# 136khz_RX_2025-06-18.net
KiCad netlist of a schematic drawn in EasyEDA Pro
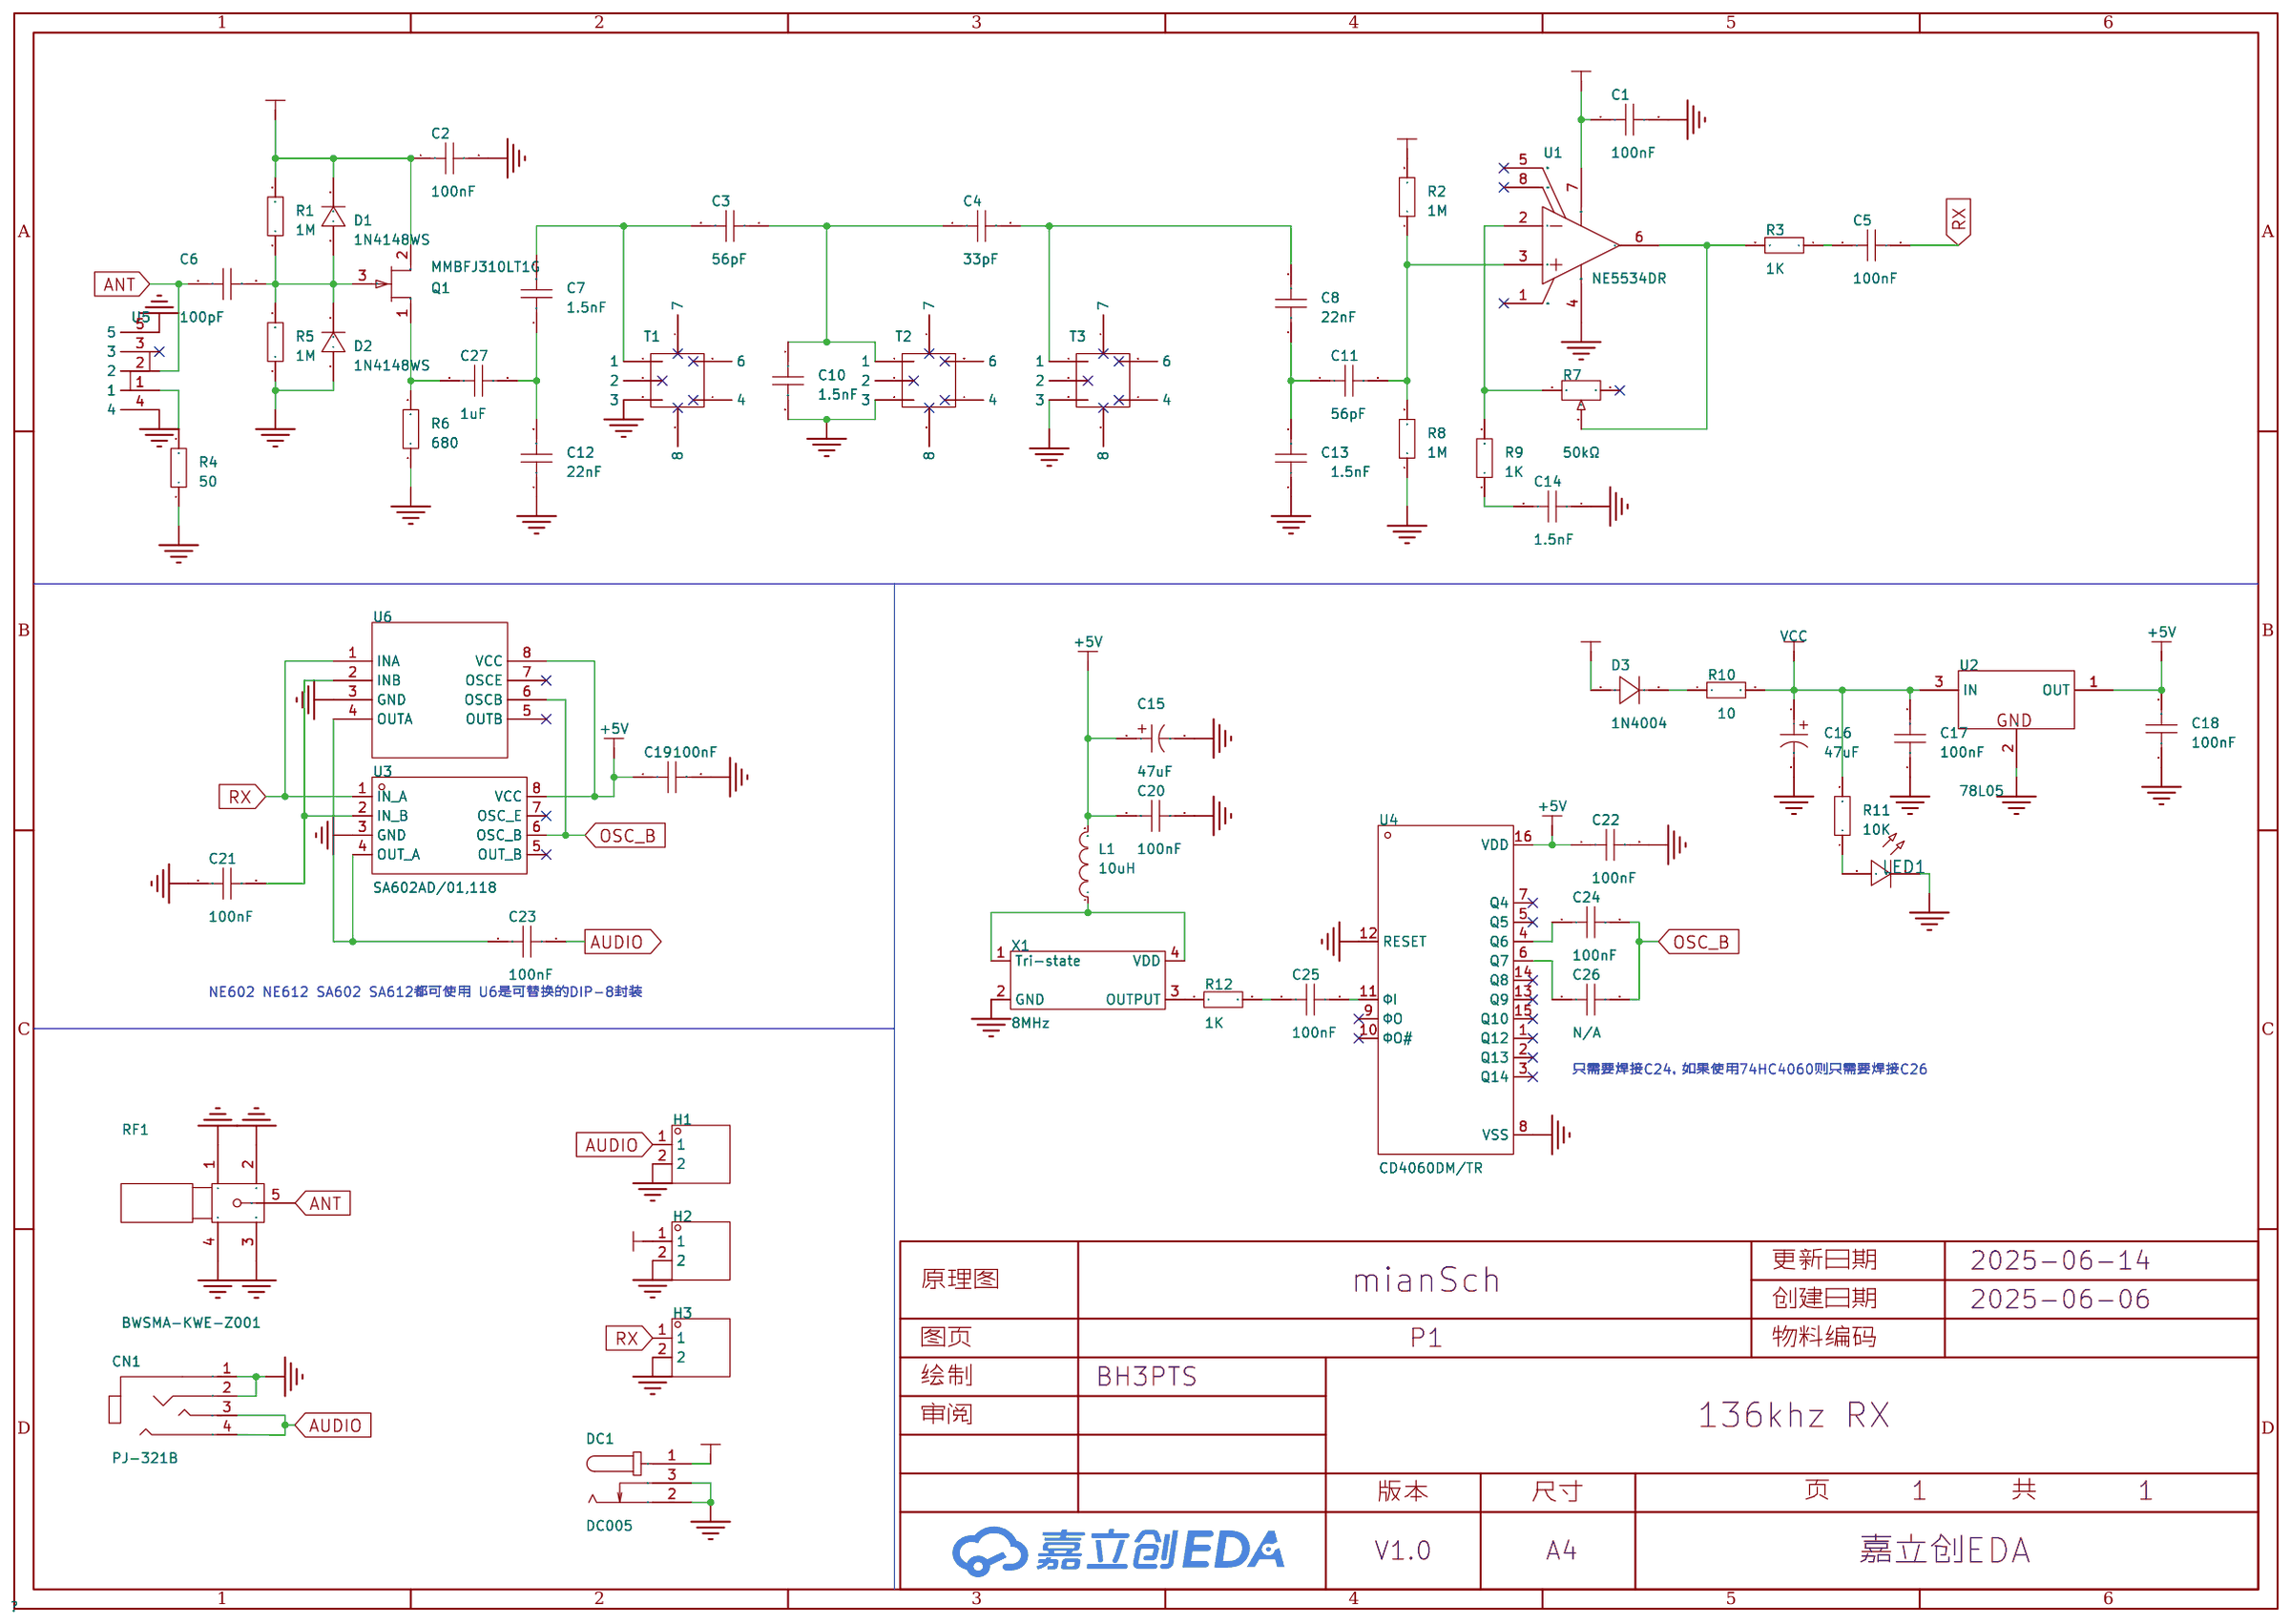
[diagram p0: schematic sheet]

(export (version "E")
  (design (tool "Eeschema 10.0.6"))
  (components
    (comp (ref "C1")
      (value "100nF")
      (footprint "easyedapro:C0805")
      (libsource (lib "easyedapro") (part "CapAcitance"))
    )
    (comp (ref "C2")
      (value "100nF")
      (footprint "easyedapro:C0805")
      (libsource (lib "easyedapro") (part "CapAcitance"))
    )
    (comp (ref "C3")
      (value "56pF")
      (footprint "easyedapro:C0805")
      (libsource (lib "easyedapro") (part "CapAcitance"))
    )
    (comp (ref "C4")
      (value "33pF")
      (footprint "easyedapro:C0805")
      (libsource (lib "easyedapro") (part "CapAcitance"))
    )
    (comp (ref "C5")
      (value "100nF")
      (footprint "easyedapro:C0805")
      (libsource (lib "easyedapro") (part "CapAcitance"))
    )
    (comp (ref "C6")
      (value "100pF")
      (footprint "easyedapro:C0805")
      (libsource (lib "easyedapro") (part "CapAcitance"))
    )
    (comp (ref "C7")
      (value "1.5nF")
      (footprint "easyedapro:C0805")
      (libsource (lib "easyedapro") (part "CapAcitance"))
    )
    (comp (ref "C8")
      (value "22nF")
      (footprint "easyedapro:C0805")
      (libsource (lib "easyedapro") (part "CapAcitance"))
    )
    (comp (ref "C10")
      (value "1.5nF")
      (footprint "easyedapro:C0805")
      (libsource (lib "easyedapro") (part "CapAcitance"))
    )
    (comp (ref "C11")
      (value "56pF")
      (footprint "easyedapro:C0805")
      (libsource (lib "easyedapro") (part "CapAcitance"))
    )
    (comp (ref "C12")
      (value "22nF")
      (footprint "easyedapro:C0805")
      (libsource (lib "easyedapro") (part "CapAcitance"))
    )
    (comp (ref "C13")
      (value "1.5nF")
      (footprint "easyedapro:C0805")
      (libsource (lib "easyedapro") (part "CapAcitance"))
    )
    (comp (ref "C14")
      (value "1.5nF")
      (footprint "easyedapro:C0805")
      (libsource (lib "easyedapro") (part "CapAcitance"))
    )
    (comp (ref "C15")
      (value "47uF")
      (footprint "easyedapro:CAP-SMD_BD6.3-L6.6-W6.6-LS7.2-FD")
      (description "容值:47uF;精度:±20%;额定电压:35V;纹波电流:16.4mA@120Hz;等效串联电阻(ESR):-;")
      (fields
        (field (name "Manufacturer Part") "RVT47UF35V67RV0039")
        (field (name "Manufacturer") "KNSCHA(科尼盛)")
      )
      (libsource (lib "easyedapro") (part "RVT47UF35V67RV0039"))
    )
    (comp (ref "C16")
      (value "47uF")
      (footprint "easyedapro:CAP-SMD_BD6.3-L6.6-W6.6-LS7.2-FD")
      (description "容值:47uF;精度:±20%;额定电压:35V;纹波电流:16.4mA@120Hz;等效串联电阻(ESR):-;")
      (fields
        (field (name "Manufacturer Part") "RVT47UF35V67RV0039")
        (field (name "Manufacturer") "KNSCHA(科尼盛)")
      )
      (libsource (lib "easyedapro") (part "RVT47UF35V67RV0039"))
    )
    (comp (ref "C17")
      (value "100nF")
      (footprint "easyedapro:C0805")
      (libsource (lib "easyedapro") (part "CapAcitance"))
    )
    (comp (ref "C18")
      (value "100nF")
      (footprint "easyedapro:C0805")
      (libsource (lib "easyedapro") (part "CapAcitance"))
    )
    (comp (ref "C19")
      (value "100nF")
      (footprint "easyedapro:C0805")
      (libsource (lib "easyedapro") (part "CapAcitance"))
    )
    (comp (ref "C20")
      (value "100nF")
      (footprint "easyedapro:C0805")
      (libsource (lib "easyedapro") (part "CapAcitance"))
    )
    (comp (ref "C21")
      (value "100nF")
      (footprint "easyedapro:C0805")
      (libsource (lib "easyedapro") (part "CapAcitance"))
    )
    (comp (ref "C22")
      (value "100nF")
      (footprint "easyedapro:C0805")
      (libsource (lib "easyedapro") (part "CapAcitance"))
    )
    (comp (ref "C23")
      (value "100nF")
      (footprint "easyedapro:C0805")
      (libsource (lib "easyedapro") (part "CapAcitance"))
    )
    (comp (ref "C24")
      (value "100nF")
      (footprint "easyedapro:C0805")
      (libsource (lib "easyedapro") (part "CapAcitance"))
    )
    (comp (ref "C25")
      (value "100nF")
      (footprint "easyedapro:C0805")
      (libsource (lib "easyedapro") (part "CapAcitance"))
    )
    (comp (ref "C26")
      (value "N/A")
      (footprint "easyedapro:C0805")
      (libsource (lib "easyedapro") (part "CapAcitance"))
    )
    (comp (ref "C27")
      (value "1uF")
      (footprint "easyedapro:C0805")
      (libsource (lib "easyedapro") (part "CapAcitance"))
    )
    (comp (ref "CN1")
      (value "PJ-321B")
      (footprint "easyedapro:AUDIO-TH_PJ-321B")
      (description "连接器类型:3.5mm耳机座;额定电流:500mA;额定电压:30V;工作温度范围:-20°C~+70°C;焊接温度(最大值):235°C;")
      (fields (field (name "Manufacturer") "XKB Connection(中国星坤)"))
      (libsource (lib "easyedapro") (part "PJ-321B"))
    )
    (comp (ref "D1")
      (value "1N4148WS")
      (footprint "easyedapro:SOD-323_L1.8-W1.3-LS2.5-RD")
      (description "二极管配置:独立式;正向压降(Vf):1.25V@150mA;直流反向耐压(Vr):100V;整流电流:150mA;反向恢复时间(trr):4ns;")
      (fields (field (name "Manufacturer") "CJ(江苏长电/长晶)"))
      (libsource (lib "easyedapro") (part "1N4148WS T4"))
    )
    (comp (ref "D2")
      (value "1N4148WS")
      (footprint "easyedapro:SOD-323_L1.8-W1.3-LS2.5-RD")
      (description "二极管配置:独立式;正向压降(Vf):1.25V@150mA;直流反向耐压(Vr):100V;整流电流:150mA;反向恢复时间(trr):4ns;")
      (fields (field (name "Manufacturer") "CJ(江苏长电/长晶)"))
      (libsource (lib "easyedapro") (part "1N4148WS T4"))
    )
    (comp (ref "D3")
      (value "1N4004")
      (footprint "easyedapro:SMA_L4.4-W2.8-LS5.4-RD")
      (description "二极管配置:独立式;正向压降(Vf):1.1V@1A;直流反向耐压(Vr):400V;整流电流:1A;")
      (fields (field (name "Manufacturer") "TWGMC(台湾迪嘉)"))
      (libsource (lib "easyedapro") (part "1N4004_C727080"))
    )
    (comp (ref "DC1")
      (value "DC005")
      (footprint "easyedapro:DC-IN-TH_DC005")
      (description "连接器类型:DC电源插座;安装方式:弯插;触点内径:2mm;触点外径:6.3mm;额定电流:500mA;额定电压:30V;工作温度范围:-25°C~+70°C;")
      (fields (field (name "Manufacturer") "SHOU HAN(首韩)"))
      (libsource (lib "easyedapro") (part "DC005_C431533"))
    )
    (comp (ref "H1")
      (value "~")
      (footprint "easyedapro:HDR-TH_2P-P2.54-V-M-1")
      (libsource (lib "easyedapro") (part "210S-1*2P L=11.6MMGold-plated black"))
    )
    (comp (ref "H2")
      (value "~")
      (footprint "easyedapro:HDR-TH_2P-P2.54-V-M-1")
      (libsource (lib "easyedapro") (part "210S-1*2P L=11.6MMGold-plated black"))
    )
    (comp (ref "H3")
      (value "~")
      (footprint "easyedapro:HDR-TH_2P-P2.54-V-M-1")
      (libsource (lib "easyedapro") (part "210S-1*2P L=11.6MMGold-plated black"))
    )
    (comp (ref "L1")
      (value "10uH")
      (footprint "easyedapro:L0603")
      (description "电感值:10uH;精度:±10%;额定电流:3mA;饱和电流(Isat):-;直流电阻(DCR):1.85Ω;")
      (fields
        (field (name "Manufacturer Part") "SDFL1608S100KTF")
        (field (name "Manufacturer") "Sunlord(顺络)")
      )
      (libsource (lib "easyedapro") (part "SDFL1608S100KTF"))
    )
    (comp (ref "LED1")
      (value "~")
      (footprint "easyedapro:LED_0603")
      (libsource (lib "easyedapro") (part "LED_R"))
    )
    (comp (ref "Q1")
      (value "MMBFJ310LT1G")
      (footprint "easyedapro:SOT-23-3_L2.9-W1.6-P1.90-LS2.8-BR")
      (description "FET类型:N沟道;栅源击穿电压(V(BR)GSS):-;功率(Pd):-;漏源导通电阻(RDS(on)):-;饱和漏源电流(Idss@Vds,Vgs=0):-;")
      (fields (field (name "Manufacturer") "onsemi(安森美)"))
      (libsource (lib "easyedapro") (part "MMBFJ310LT1G"))
    )
    (comp (ref "R1") (value "1M") (footprint "easyedapro:R0805") (libsource (lib "easyedapro") (part "电阻")))
    (comp (ref "R2") (value "1M") (footprint "easyedapro:R0805") (libsource (lib "easyedapro") (part "电阻")))
    (comp (ref "R3") (value "1K") (footprint "easyedapro:R0805") (libsource (lib "easyedapro") (part "电阻")))
    (comp (ref "R4") (value "50") (footprint "easyedapro:R0805") (libsource (lib "easyedapro") (part "电阻")))
    (comp (ref "R5") (value "1M") (footprint "easyedapro:R0805") (libsource (lib "easyedapro") (part "电阻")))
    (comp (ref "R6") (value "680") (footprint "easyedapro:R0805") (libsource (lib "easyedapro") (part "电阻")))
    (comp (ref "R7")
      (value "50kΩ")
      (footprint "easyedapro:RES-ADJ-TH_3P-L7.1-W6.9-P2.50-L_3362P")
      (description "阻值:50kΩ;精度:±10%;")
      (fields (field (name "Manufacturer Part") "3362P-1-503") (field (name "Manufacturer") "BOCHEN(博晨)"))
      (libsource (lib "easyedapro") (part "3362P-1-503"))
    )
    (comp (ref "R8") (value "1M") (footprint "easyedapro:R0805") (libsource (lib "easyedapro") (part "电阻")))
    (comp (ref "R9") (value "1K") (footprint "easyedapro:R0805") (libsource (lib "easyedapro") (part "电阻")))
    (comp (ref "R10") (value "10") (footprint "easyedapro:R1206") (libsource (lib "easyedapro") (part "电阻")))
    (comp (ref "R11") (value "10K") (footprint "easyedapro:R0805") (libsource (lib "easyedapro") (part "电阻")))
    (comp (ref "R12") (value "1K") (footprint "easyedapro:R0805") (libsource (lib "easyedapro") (part "电阻")))
    (comp (ref "RF1")
      (value "BWSMA-KWE-Z001")
      (footprint "easyedapro:SMA-TH_BWSMA-KWE-Z001")
      (fields (field (name "Manufacturer") "BAT WIRELESS(蝙蝠无线)"))
      (libsource (lib "easyedapro") (part "BWSMA-KWE-Z001"))
    )
    (comp (ref "T1") (value "~") (footprint "easyedapro:TP702") (libsource (lib "easyedapro") (part "TP702")))
    (comp (ref "T2") (value "~") (footprint "easyedapro:TP702") (libsource (lib "easyedapro") (part "TP702")))
    (comp (ref "T3") (value "~") (footprint "easyedapro:TP702") (libsource (lib "easyedapro") (part "TP702")))
    (comp (ref "U1")
      (value "NE5534DR")
      (footprint "easyedapro:SOIC-8_L5.0-W4.0-P1.27-LS6.0-BL")
      (description "放大器数:单路;轨到轨:-;增益带宽积(GBP):-;输入失调电压(Vos):4mV;压摆率(SR):13V/us;输入偏置电流(Ib):1.5uA;")
      (fields (field (name "Manufacturer") "TI(德州仪器)"))
      (libsource (lib "easyedapro") (part "NE5534DR"))
    )
    (comp (ref "U2")
      (value "78L05")
      (footprint "easyedapro:SOT-89-3_L4.5-W2.5-P1.50-LS4.2-BR")
      (description "输出类型:固定;最大输入电压:30V;输出电压:5V;输出电流:100mA;电源纹波抑制比(PSRR):49dB@(120Hz);输出极性:正极;")
      (fields (field (name "Manufacturer") "UMW(友台半导体)"))
      (libsource (lib "easyedapro") (part "UMW78L05"))
    )
    (comp (ref "U3")
      (value "SA602AD/01,118")
      (footprint "easyedapro:SOP-8_L4.9-W3.9-P1.27-LS6.0-BL")
      (description "应用领域:手机；VHF；UHF；HF;频率范围:-;增益:17dB;噪声系数:5dB;")
      (fields (field (name "Manufacturer") "NXP(恩智浦)"))
      (libsource (lib "easyedapro") (part "SA602AD/01,118"))
    )
    (comp (ref "U4")
      (value "CD4060DM/TR")
      (footprint "easyedapro:SOP-16_L9.9-W3.9-P1.27-LS6.0-BL")
      (description "CD4000系列  CMOS 14 级纹波进位二进制计数器/除法器和振荡器")
      (fields (field (name "Manufacturer") "HGSEMI(华冠)"))
      (libsource (lib "easyedapro") (part "CD4060DM/TR"))
    )
    (comp (ref "U5")
      (value "~")
      (footprint "easyedapro:SS-12D07G3")
      (description "3脚2档 柄高3MM")
      (libsource (lib "easyedapro") (part "SS-12D07G3"))
    )
    (comp (ref "U6")
      (value "~")
      (footprint "easyedapro:DIP-8_L9.2-W6.4-P2.54-LS7.6-BL")
      (fields (field (name "Manufacturer") "ddsddp-"))
      (libsource (lib "easyedapro") (part "ne602"))
    )
    (comp (ref "X1")
      (value "8MHz")
      (footprint "easyedapro:OSC-SMD_4P-L3.2-W2.5-BL")
      (description "频率:8MHz;常温频差:±10ppm;输出模式:CMOS;工作电压:5V;频率稳定度:±20ppm;")
      (fields
        (field (name "Manufacturer Part") "OH2EL89CFI-111YLC-8M")
        (field (name "Manufacturer") "YXC(扬兴晶振)")
      )
      (libsource (lib "easyedapro") (part "OH2EL89CFI-111YLC-8M"))
    )
  )
  (nets
    (net (code "1") (name "+5V") (class "Default")
      (node (ref "C15") (pin "1") (pinfunction "1_1") (pintype "input"))
      (node (ref "C18") (pin "2") (pinfunction "2_2") (pintype "input"))
      (node (ref "C19") (pin "1") (pinfunction "1_1") (pintype "input"))
      (node (ref "C20") (pin "2") (pinfunction "2_2") (pintype "input"))
      (node (ref "C22") (pin "1") (pinfunction "1_1") (pintype "input"))
      (node (ref "L1") (pin "2") (pinfunction "2_2") (pintype "unspecified"))
      (node (ref "U2") (pin "1") (pinfunction "OUT_1") (pintype "unspecified"))
      (node (ref "U3") (pin "8") (pinfunction "VCC_8") (pintype "unspecified"))
      (node (ref "U4") (pin "16") (pinfunction "VDD_16") (pintype "unspecified"))
      (node (ref "U6") (pin "8") (pinfunction "VCC_8") (pintype "input"))
    )
    (net (code "2") (name "ANT") (class "Default")
      (node (ref "C6") (pin "1") (pinfunction "1_1") (pintype "input"))
      (node (ref "RF1") (pin "5") (pinfunction "5_5") (pintype "unspecified"))
      (node (ref "U5") (pin "2") (pinfunction "2_2") (pintype "input"))
    )
    (net (code "3") (name "AUDIO") (class "Default")
      (node (ref "C23") (pin "1") (pinfunction "1_1") (pintype "input"))
      (node (ref "CN1") (pin "3") (pinfunction "3_3") (pintype "unspecified"))
      (node (ref "CN1") (pin "4") (pinfunction "4_4") (pintype "unspecified"))
      (node (ref "H1") (pin "1") (pinfunction "1_1") (pintype "unspecified"))
    )
    (net (code "4") (name "GND") (class "Default")
      (node (ref "C1") (pin "2") (pinfunction "2_2") (pintype "input"))
      (node (ref "C10") (pin "2") (pinfunction "2_2") (pintype "input"))
      (node (ref "C12") (pin "1") (pinfunction "1_1") (pintype "input"))
      (node (ref "C13") (pin "1") (pinfunction "1_1") (pintype "input"))
      (node (ref "C14") (pin "1") (pinfunction "1_1") (pintype "input"))
      (node (ref "C15") (pin "2") (pinfunction "2_2") (pintype "input"))
      (node (ref "C16") (pin "2") (pinfunction "2_2") (pintype "input"))
      (node (ref "C17") (pin "1") (pinfunction "1_1") (pintype "input"))
      (node (ref "C18") (pin "1") (pinfunction "1_1") (pintype "input"))
      (node (ref "C19") (pin "2") (pinfunction "2_2") (pintype "input"))
      (node (ref "C2") (pin "2") (pinfunction "2_2") (pintype "input"))
      (node (ref "C20") (pin "1") (pinfunction "1_1") (pintype "input"))
      (node (ref "C21") (pin "1") (pinfunction "1_1") (pintype "input"))
      (node (ref "C22") (pin "2") (pinfunction "2_2") (pintype "input"))
      (node (ref "CN1") (pin "1") (pinfunction "1_1") (pintype "unspecified"))
      (node (ref "CN1") (pin "2") (pinfunction "2_2") (pintype "unspecified"))
      (node (ref "D2") (pin "2") (pinfunction "A_2") (pintype "unspecified"))
      (node (ref "DC1") (pin "2") (pinfunction "2_2") (pintype "unspecified"))
      (node (ref "DC1") (pin "3") (pinfunction "3_3") (pintype "unspecified"))
      (node (ref "H1") (pin "2") (pinfunction "2_2") (pintype "unspecified"))
      (node (ref "H2") (pin "2") (pinfunction "2_2") (pintype "unspecified"))
      (node (ref "H3") (pin "2") (pinfunction "2_2") (pintype "unspecified"))
      (node (ref "LED1") (pin "1") (pinfunction "C_1") (pintype "input"))
      (node (ref "R4") (pin "1") (pinfunction "1_1") (pintype "input"))
      (node (ref "R5") (pin "1") (pinfunction "1_1") (pintype "input"))
      (node (ref "R6") (pin "1") (pinfunction "1_1") (pintype "input"))
      (node (ref "R8") (pin "1") (pinfunction "1_1") (pintype "input"))
      (node (ref "RF1") (pin "1") (pinfunction "1_1") (pintype "unspecified"))
      (node (ref "RF1") (pin "2") (pinfunction "2_2") (pintype "unspecified"))
      (node (ref "RF1") (pin "3") (pinfunction "3_3") (pintype "unspecified"))
      (node (ref "RF1") (pin "4") (pinfunction "4_4") (pintype "unspecified"))
      (node (ref "T1") (pin "3") (pinfunction "3_3") (pintype "input"))
      (node (ref "T2") (pin "3") (pinfunction "3_3") (pintype "input"))
      (node (ref "T3") (pin "3") (pinfunction "3_3") (pintype "input"))
      (node (ref "U1") (pin "4") (pinfunction "VCC-_4") (pintype "unspecified"))
      (node (ref "U2") (pin "2") (pinfunction "GND_2") (pintype "unspecified"))
      (node (ref "U3") (pin "3") (pinfunction "GND_3") (pintype "unspecified"))
      (node (ref "U4") (pin "12") (pinfunction "RESET_12") (pintype "unspecified"))
      (node (ref "U4") (pin "8") (pinfunction "VSS_8") (pintype "unspecified"))
      (node (ref "U5") (pin "4") (pinfunction "4_4") (pintype "input"))
      (node (ref "U5") (pin "5") (pinfunction "5_5") (pintype "input"))
      (node (ref "U6") (pin "3") (pinfunction "GND_3") (pintype "input"))
      (node (ref "X1") (pin "2") (pinfunction "GND_2") (pintype "unspecified"))
    )
    (net (code "5") (name "Net-(C3-Pad2)") (class "Default")
      (node (ref "C3") (pin "2") (pinfunction "2_2") (pintype "input"))
      (node (ref "C7") (pin "2") (pinfunction "2_2") (pintype "input"))
      (node (ref "T1") (pin "1") (pinfunction "1_1") (pintype "input"))
    )
    (net (code "6") (name "Net-(C4-Pad2)") (class "Default")
      (node (ref "C4") (pin "2") (pinfunction "2_2") (pintype "input"))
      (node (ref "C8") (pin "2") (pinfunction "2_2") (pintype "input"))
      (node (ref "T3") (pin "1") (pinfunction "1_1") (pintype "input"))
    )
    (net (code "7") (name "Net-(C5-Pad1)") (class "Default")
      (node (ref "C5") (pin "1") (pinfunction "1_1") (pintype "input"))
      (node (ref "R3") (pin "1") (pinfunction "1_1") (pintype "input"))
    )
    (net (code "8") (name "Net-(C10-Pad1)") (class "Default")
      (node (ref "C10") (pin "1") (pinfunction "1_1") (pintype "input"))
      (node (ref "C3") (pin "1") (pinfunction "1_1") (pintype "input"))
      (node (ref "C4") (pin "1") (pinfunction "1_1") (pintype "input"))
      (node (ref "T2") (pin "1") (pinfunction "1_1") (pintype "input"))
    )
    (net (code "9") (name "Net-(C11-Pad1)") (class "Default")
      (node (ref "C11") (pin "1") (pinfunction "1_1") (pintype "input"))
      (node (ref "C13") (pin "2") (pinfunction "2_2") (pintype "input"))
      (node (ref "C8") (pin "1") (pinfunction "1_1") (pintype "input"))
    )
    (net (code "10") (name "Net-(C12-Pad2)") (class "Default")
      (node (ref "C12") (pin "2") (pinfunction "2_2") (pintype "input"))
      (node (ref "C27") (pin "2") (pinfunction "2_2") (pintype "input"))
      (node (ref "C7") (pin "1") (pinfunction "1_1") (pintype "input"))
    )
    (net (code "11") (name "Net-(C14-Pad2)") (class "Default")
      (node (ref "C14") (pin "2") (pinfunction "2_2") (pintype "input"))
      (node (ref "R9") (pin "1") (pinfunction "1_1") (pintype "input"))
    )
    (net (code "12") (name "Net-(C25-Pad1)") (class "Default")
      (node (ref "C25") (pin "1") (pinfunction "1_1") (pintype "input"))
      (node (ref "R12") (pin "2") (pinfunction "2_2") (pintype "input"))
    )
    (net (code "13") (name "Net-(D1-A)") (class "Default")
      (node (ref "C6") (pin "2") (pinfunction "2_2") (pintype "input"))
      (node (ref "D1") (pin "2") (pinfunction "A_2") (pintype "unspecified"))
      (node (ref "D2") (pin "1") (pinfunction "K_1") (pintype "unspecified"))
      (node (ref "Q1") (pin "3") (pinfunction "G_3") (pintype "unspecified"))
      (node (ref "R1") (pin "1") (pinfunction "1_1") (pintype "input"))
      (node (ref "R5") (pin "2") (pinfunction "2_2") (pintype "input"))
    )
    (net (code "14") (name "Net-(D3-K)") (class "Default")
      (node (ref "D3") (pin "1") (pinfunction "K_1") (pintype "unspecified"))
      (node (ref "R10") (pin "1") (pinfunction "1_1") (pintype "input"))
    )
    (net (code "15") (name "Net-(LED1-A)") (class "Default")
      (node (ref "LED1") (pin "2") (pinfunction "A_2") (pintype "input"))
      (node (ref "R11") (pin "1") (pinfunction "1_1") (pintype "input"))
    )
    (net (code "16") (name "Net-(Q1-D)") (class "Default")
      (node (ref "C27") (pin "1") (pinfunction "1_1") (pintype "input"))
      (node (ref "Q1") (pin "1") (pinfunction "D_1") (pintype "unspecified"))
      (node (ref "R6") (pin "2") (pinfunction "2_2") (pintype "input"))
    )
    (net (code "17") (name "Net-(R4-Pad2)") (class "Default")
      (node (ref "R4") (pin "2") (pinfunction "2_2") (pintype "input"))
      (node (ref "U5") (pin "1") (pinfunction "1_1") (pintype "input"))
    )
    (net (code "18") (name "Net-(U1-IN+)") (class "Default")
      (node (ref "C11") (pin "2") (pinfunction "2_2") (pintype "input"))
      (node (ref "R2") (pin "1") (pinfunction "1_1") (pintype "input"))
      (node (ref "R8") (pin "2") (pinfunction "2_2") (pintype "input"))
      (node (ref "U1") (pin "3") (pinfunction "IN+_3") (pintype "unspecified"))
    )
    (net (code "19") (name "Net-(U1-IN-)") (class "Default")
      (node (ref "R7") (pin "3") (pinfunction "3_3") (pintype "input"))
      (node (ref "R9") (pin "2") (pinfunction "2_2") (pintype "input"))
      (node (ref "U1") (pin "2") (pinfunction "IN-_2") (pintype "unspecified"))
    )
    (net (code "20") (name "Net-(U1-OUT)") (class "Default")
      (node (ref "R3") (pin "2") (pinfunction "2_2") (pintype "input"))
      (node (ref "R7") (pin "2") (pinfunction "2_2") (pintype "input"))
      (node (ref "U1") (pin "6") (pinfunction "OUT_6") (pintype "output"))
    )
    (net (code "21") (name "Net-(U3-IN_B)") (class "Default")
      (node (ref "C21") (pin "2") (pinfunction "2_2") (pintype "input"))
      (node (ref "U3") (pin "2") (pinfunction "IN_B_2") (pintype "unspecified"))
      (node (ref "U6") (pin "2") (pinfunction "INB_2") (pintype "input"))
    )
    (net (code "22") (name "Net-(U3-OUT_A)") (class "Default")
      (node (ref "C23") (pin "2") (pinfunction "2_2") (pintype "input"))
      (node (ref "U3") (pin "4") (pinfunction "OUT_A_4") (pintype "unspecified"))
      (node (ref "U6") (pin "4") (pinfunction "OUTA_4") (pintype "input"))
    )
    (net (code "23") (name "Net-(U4-Q6)") (class "Default")
      (node (ref "C24") (pin "1") (pinfunction "1_1") (pintype "input"))
      (node (ref "U4") (pin "4") (pinfunction "Q6_4") (pintype "unspecified"))
    )
    (net (code "24") (name "Net-(U4-Q7)") (class "Default")
      (node (ref "C26") (pin "1") (pinfunction "1_1") (pintype "input"))
      (node (ref "U4") (pin "6") (pinfunction "Q7_6") (pintype "unspecified"))
    )
    (net (code "25") (name "Net-(U4-ФI)") (class "Default")
      (node (ref "C25") (pin "2") (pinfunction "2_2") (pintype "input"))
      (node (ref "U4") (pin "11") (pinfunction "ФI_11") (pintype "unspecified"))
    )
    (net (code "26") (name "Net-(X1-OUTPUT)") (class "Default")
      (node (ref "R12") (pin "1") (pinfunction "1_1") (pintype "input"))
      (node (ref "X1") (pin "3") (pinfunction "OUTPUT_3") (pintype "unspecified"))
    )
    (net (code "27") (name "Net-(X1-Tri-state)") (class "Default")
      (node (ref "L1") (pin "1") (pinfunction "1_1") (pintype "unspecified"))
      (node (ref "X1") (pin "1") (pinfunction "Tri-state_1") (pintype "unspecified"))
      (node (ref "X1") (pin "4") (pinfunction "VDD_4") (pintype "unspecified"))
    )
    (net (code "28") (name "OSC_B") (class "Default")
      (node (ref "C24") (pin "2") (pinfunction "2_2") (pintype "input"))
      (node (ref "C26") (pin "2") (pinfunction "2_2") (pintype "input"))
      (node (ref "U3") (pin "6") (pinfunction "OSC_B_6") (pintype "unspecified"))
      (node (ref "U6") (pin "6") (pinfunction "OSCB_6") (pintype "input"))
    )
    (net (code "29") (name "RX") (class "Default")
      (node (ref "C5") (pin "2") (pinfunction "2_2") (pintype "input"))
      (node (ref "H3") (pin "1") (pinfunction "1_1") (pintype "unspecified"))
      (node (ref "U3") (pin "1") (pinfunction "IN_A_1") (pintype "unspecified"))
      (node (ref "U6") (pin "1") (pinfunction "INA_1") (pintype "input"))
    )
    (net (code "30") (name "VCC") (class "Default")
      (node (ref "C1") (pin "1") (pinfunction "1_1") (pintype "input"))
      (node (ref "C16") (pin "1") (pinfunction "1_1") (pintype "input"))
      (node (ref "C17") (pin "2") (pinfunction "2_2") (pintype "input"))
      (node (ref "C2") (pin "1") (pinfunction "1_1") (pintype "input"))
      (node (ref "D1") (pin "1") (pinfunction "K_1") (pintype "unspecified"))
      (node (ref "Q1") (pin "2") (pinfunction "S_2") (pintype "unspecified"))
      (node (ref "R1") (pin "2") (pinfunction "2_2") (pintype "input"))
      (node (ref "R10") (pin "2") (pinfunction "2_2") (pintype "input"))
      (node (ref "R11") (pin "2") (pinfunction "2_2") (pintype "input"))
      (node (ref "R2") (pin "2") (pinfunction "2_2") (pintype "input"))
      (node (ref "U1") (pin "7") (pinfunction "VCC+_7") (pintype "unspecified"))
      (node (ref "U2") (pin "3") (pinfunction "IN_3") (pintype "unspecified"))
    )
    (net (code "31") (name "VIN") (class "Default")
      (node (ref "D3") (pin "2") (pinfunction "A_2") (pintype "unspecified"))
      (node (ref "DC1") (pin "1") (pinfunction "1_1") (pintype "unspecified"))
      (node (ref "H2") (pin "1") (pinfunction "1_1") (pintype "unspecified"))
    )
    (net (code "32") (name "unconnected-(R7-Pad1)") (class "Default")
      (node (ref "R7") (pin "1") (pinfunction "1_1") (pintype "input+no_connect"))
    )
    (net (code "33") (name "unconnected-(T1-Pad2)") (class "Default")
      (node (ref "T1") (pin "2") (pinfunction "2_2") (pintype "input+no_connect"))
    )
    (net (code "34") (name "unconnected-(T1-Pad4)") (class "Default")
      (node (ref "T1") (pin "4") (pinfunction "4_4") (pintype "input+no_connect"))
    )
    (net (code "35") (name "unconnected-(T1-Pad6)") (class "Default")
      (node (ref "T1") (pin "6") (pinfunction "6_6") (pintype "input+no_connect"))
    )
    (net (code "36") (name "unconnected-(T1-Pad7)") (class "Default")
      (node (ref "T1") (pin "7") (pinfunction "7_7") (pintype "input+no_connect"))
    )
    (net (code "37") (name "unconnected-(T1-Pad8)") (class "Default")
      (node (ref "T1") (pin "8") (pinfunction "8_8") (pintype "input+no_connect"))
    )
    (net (code "38") (name "unconnected-(T2-Pad2)") (class "Default")
      (node (ref "T2") (pin "2") (pinfunction "2_2") (pintype "input+no_connect"))
    )
    (net (code "39") (name "unconnected-(T2-Pad4)") (class "Default")
      (node (ref "T2") (pin "4") (pinfunction "4_4") (pintype "input+no_connect"))
    )
    (net (code "40") (name "unconnected-(T2-Pad6)") (class "Default")
      (node (ref "T2") (pin "6") (pinfunction "6_6") (pintype "input+no_connect"))
    )
    (net (code "41") (name "unconnected-(T2-Pad7)") (class "Default")
      (node (ref "T2") (pin "7") (pinfunction "7_7") (pintype "input+no_connect"))
    )
    (net (code "42") (name "unconnected-(T2-Pad8)") (class "Default")
      (node (ref "T2") (pin "8") (pinfunction "8_8") (pintype "input+no_connect"))
    )
    (net (code "43") (name "unconnected-(T3-Pad2)") (class "Default")
      (node (ref "T3") (pin "2") (pinfunction "2_2") (pintype "input+no_connect"))
    )
    (net (code "44") (name "unconnected-(T3-Pad4)") (class "Default")
      (node (ref "T3") (pin "4") (pinfunction "4_4") (pintype "input+no_connect"))
    )
    (net (code "45") (name "unconnected-(T3-Pad6)") (class "Default")
      (node (ref "T3") (pin "6") (pinfunction "6_6") (pintype "input+no_connect"))
    )
    (net (code "46") (name "unconnected-(T3-Pad7)") (class "Default")
      (node (ref "T3") (pin "7") (pinfunction "7_7") (pintype "input+no_connect"))
    )
    (net (code "47") (name "unconnected-(T3-Pad8)") (class "Default")
      (node (ref "T3") (pin "8") (pinfunction "8_8") (pintype "input+no_connect"))
    )
    (net (code "48") (name "unconnected-(U1-BALANCE-Pad1)") (class "Default")
      (node (ref "U1") (pin "1") (pinfunction "BALANCE_1") (pintype "unspecified+no_connect"))
    )
    (net (code "49") (name "unconnected-(U1-COMP-Pad5)") (class "Default")
      (node (ref "U1") (pin "5") (pinfunction "COMP_5") (pintype "unspecified+no_connect"))
    )
    (net (code "50") (name "unconnected-(U1-COMPBAL-Pad8)") (class "Default")
      (node (ref "U1") (pin "8") (pinfunction "COMPBAL_8") (pintype "unspecified+no_connect"))
    )
    (net (code "51") (name "unconnected-(U3-OSC_E-Pad7)") (class "Default")
      (node (ref "U3") (pin "7") (pinfunction "OSC_E_7") (pintype "unspecified+no_connect"))
    )
    (net (code "52") (name "unconnected-(U3-OUT_B-Pad5)") (class "Default")
      (node (ref "U3") (pin "5") (pinfunction "OUT_B_5") (pintype "unspecified+no_connect"))
    )
    (net (code "53") (name "unconnected-(U4-Q4-Pad7)") (class "Default")
      (node (ref "U4") (pin "7") (pinfunction "Q4_7") (pintype "unspecified+no_connect"))
    )
    (net (code "54") (name "unconnected-(U4-Q5-Pad5)") (class "Default")
      (node (ref "U4") (pin "5") (pinfunction "Q5_5") (pintype "unspecified+no_connect"))
    )
    (net (code "55") (name "unconnected-(U4-Q8-Pad14)") (class "Default")
      (node (ref "U4") (pin "14") (pinfunction "Q8_14") (pintype "unspecified+no_connect"))
    )
    (net (code "56") (name "unconnected-(U4-Q9-Pad13)") (class "Default")
      (node (ref "U4") (pin "13") (pinfunction "Q9_13") (pintype "unspecified+no_connect"))
    )
    (net (code "57") (name "unconnected-(U4-Q10-Pad15)") (class "Default")
      (node (ref "U4") (pin "15") (pinfunction "Q10_15") (pintype "unspecified+no_connect"))
    )
    (net (code "58") (name "unconnected-(U4-Q12-Pad1)") (class "Default")
      (node (ref "U4") (pin "1") (pinfunction "Q12_1") (pintype "unspecified+no_connect"))
    )
    (net (code "59") (name "unconnected-(U4-Q13-Pad2)") (class "Default")
      (node (ref "U4") (pin "2") (pinfunction "Q13_2") (pintype "unspecified+no_connect"))
    )
    (net (code "60") (name "unconnected-(U4-Q14-Pad3)") (class "Default")
      (node (ref "U4") (pin "3") (pinfunction "Q14_3") (pintype "unspecified+no_connect"))
    )
    (net (code "61") (name "unconnected-(U4-ФO#-Pad10)") (class "Default")
      (node (ref "U4") (pin "10") (pinfunction "ФO#_10") (pintype "unspecified+no_connect"))
    )
    (net (code "62") (name "unconnected-(U4-ФO-Pad9)") (class "Default")
      (node (ref "U4") (pin "9") (pinfunction "ФO_9") (pintype "unspecified+no_connect"))
    )
    (net (code "63") (name "unconnected-(U5-Pad3)") (class "Default")
      (node (ref "U5") (pin "3") (pinfunction "3_3") (pintype "input+no_connect"))
    )
    (net (code "64") (name "unconnected-(U6-OSCE-Pad7)") (class "Default")
      (node (ref "U6") (pin "7") (pinfunction "OSCE_7") (pintype "input+no_connect"))
    )
    (net (code "65") (name "unconnected-(U6-OUTB-Pad5)") (class "Default")
      (node (ref "U6") (pin "5") (pinfunction "OUTB_5") (pintype "input+no_connect"))
    )
  )
)
